# STM3205P_Connectors.net
KiCad netlist of a schematic drawn in Altium Designer
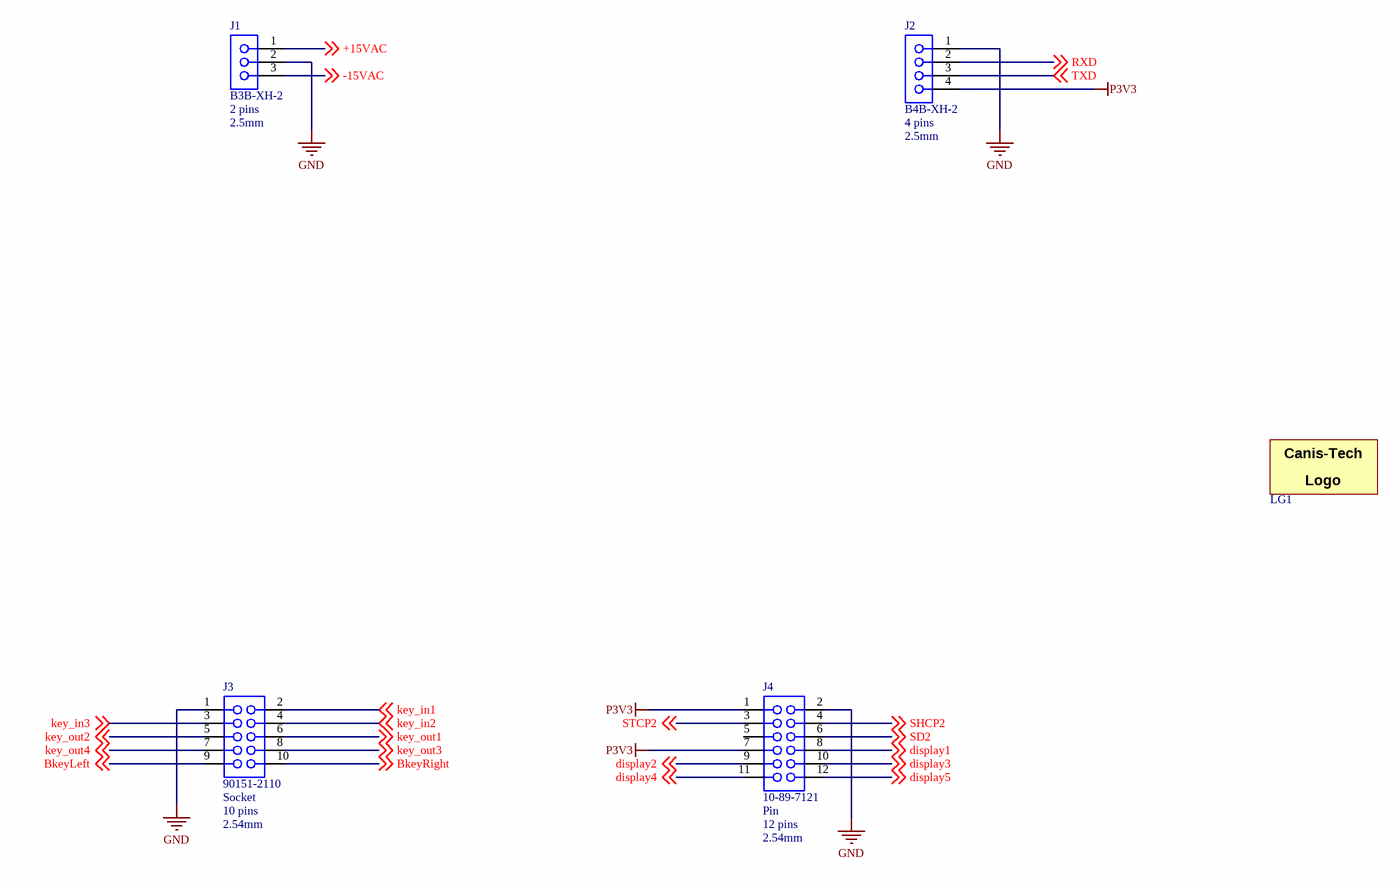
[diagram p0: STM3205P_Connectors.SchDoc]

(export (version "E")
  (design (tool "Eeschema 10.0.6"))
  (components
    (comp (ref "J1")
      (value "B3B-XH-2")
      (footprint "CONXH03STRMALE_2.5")
      (description "XH Connector 3 POS HDR VERT 2.5mm")
      (fields
        (field (name "PARTNUMBER1") "B3B-XH-2")
        (field (name "PINS") "2 pins")
        (field (name "PITCH") "2.5mm")
        (field (name "PUBLISHER") "Lucas Moraes")
      )
      (libsource (lib "XHConnector") (part "B3B-XH-2"))
    )
    (comp (ref "J2")
      (value "B4B-XH-2")
      (footprint "CONXH04STRMALE_2.5")
      (description "XH Connector 4 POS HDR VERT 2.5mm")
      (fields
        (field (name "PARTNUMBER1") "B4B-XH-2")
        (field (name "PINS") "4 pins")
        (field (name "PITCH") "2.5mm")
        (field (name "PUBLISHER") "Lucas Moraes")
      )
      (libsource (lib "XHConnector") (part "B4B-XH-2"))
    )
    (comp (ref "J3")
      (value "90151-2110")
      (footprint "CONDIL10STRFEMALE_100_100")
      (description "Headers & Wire Housings C-Grid PCB Conn Dual Row Vertical 10Ckt")
      (fields
        (field (name "PARTNUMBER1") "90151-2110")
        (field (name "TYPE") "Socket")
        (field (name "PINS") "10 pins")
        (field (name "PITCH") "2.54mm")
        (field (name "PUBLISHER") "Lucas Moraes")
      )
      (libsource (lib "HeaderSocket") (part "90151-2110"))
    )
    (comp (ref "J4")
      (value "10-89-7121")
      (footprint "CONDIL12STRMALE_100_100")
      (description "Headers & Wire Housings C-Grid PCB Conn SR V onn SR Vt Tn-A 12Ckt")
      (fields
        (field (name "PARTNUMBER1") "10-89-7121")
        (field (name "TYPE") "Pin")
        (field (name "PINS") "12 pins")
        (field (name "PITCH") "2.54mm")
        (field (name "PUBLISHER") "Lucas Moraes")
      )
      (libsource (lib "HeaderPin") (part "10-89-7121"))
    )
    (comp (ref "LG1")
      (value "Canis-Tech Logo")
      (footprint "CT Logo 400th")
      (description "Canis-Tech LOGO")
      (fields (field (name "PUBLISHER") "Lucas Moraes"))
      (libsource (lib "LocalSymbols") (part "Canis-Tech Logo"))
    )
  )
  (nets
    (net (code "1") (name "+15VAC") (class "Default")
      (node (ref "J1") (pin "1") (pinfunction "1_1") (pintype "passive"))
    )
    (net (code "2") (name "-15VAC") (class "Default")
      (node (ref "J1") (pin "3") (pinfunction "3_3") (pintype "passive"))
    )
    (net (code "3") (name "BkeyLeft") (class "Default")
      (node (ref "J3") (pin "9") (pinfunction "9_9") (pintype "passive"))
    )
    (net (code "4") (name "BkeyRight") (class "Default")
      (node (ref "J3") (pin "10") (pinfunction "10_10") (pintype "passive"))
    )
    (net (code "5") (name "GND") (class "Default")
      (node (ref "J1") (pin "2") (pinfunction "2_2") (pintype "passive"))
      (node (ref "J2") (pin "1") (pinfunction "1_1") (pintype "passive"))
      (node (ref "J3") (pin "1") (pinfunction "1_1") (pintype "passive"))
      (node (ref "J4") (pin "2") (pinfunction "2_2") (pintype "passive"))
    )
    (net (code "6") (name "P3V3") (class "Default")
      (node (ref "J2") (pin "4") (pinfunction "4_4") (pintype "passive"))
      (node (ref "J4") (pin "1") (pinfunction "1_1") (pintype "passive"))
      (node (ref "J4") (pin "7") (pinfunction "7_7") (pintype "passive"))
    )
    (net (code "7") (name "RXD") (class "Default")
      (node (ref "J2") (pin "2") (pinfunction "2_2") (pintype "passive"))
    )
    (net (code "8") (name "SD2") (class "Default")
      (node (ref "J4") (pin "6") (pinfunction "6_6") (pintype "passive"))
    )
    (net (code "9") (name "SHCP2") (class "Default")
      (node (ref "J4") (pin "4") (pinfunction "4_4") (pintype "passive"))
    )
    (net (code "10") (name "STCP2") (class "Default")
      (node (ref "J4") (pin "3") (pinfunction "3_3") (pintype "passive"))
    )
    (net (code "11") (name "TXD") (class "Default")
      (node (ref "J2") (pin "3") (pinfunction "3_3") (pintype "passive"))
    )
    (net (code "12") (name "display1") (class "Default")
      (node (ref "J4") (pin "8") (pinfunction "8_8") (pintype "passive"))
    )
    (net (code "13") (name "display2") (class "Default")
      (node (ref "J4") (pin "9") (pinfunction "9_9") (pintype "passive"))
    )
    (net (code "14") (name "display3") (class "Default")
      (node (ref "J4") (pin "10") (pinfunction "10_10") (pintype "passive"))
    )
    (net (code "15") (name "display4") (class "Default")
      (node (ref "J4") (pin "11") (pinfunction "11_11") (pintype "passive"))
    )
    (net (code "16") (name "display5") (class "Default")
      (node (ref "J4") (pin "12") (pinfunction "12_12") (pintype "passive"))
    )
    (net (code "17") (name "key_in1") (class "Default")
      (node (ref "J3") (pin "2") (pinfunction "2_2") (pintype "passive"))
    )
    (net (code "18") (name "key_in2") (class "Default")
      (node (ref "J3") (pin "4") (pinfunction "4_4") (pintype "passive"))
    )
    (net (code "19") (name "key_in3") (class "Default")
      (node (ref "J3") (pin "3") (pinfunction "3_3") (pintype "passive"))
    )
    (net (code "20") (name "key_out1") (class "Default")
      (node (ref "J3") (pin "6") (pinfunction "6_6") (pintype "passive"))
    )
    (net (code "21") (name "key_out2") (class "Default")
      (node (ref "J3") (pin "5") (pinfunction "5_5") (pintype "passive"))
    )
    (net (code "22") (name "key_out3") (class "Default")
      (node (ref "J3") (pin "8") (pinfunction "8_8") (pintype "passive"))
    )
    (net (code "23") (name "key_out4") (class "Default")
      (node (ref "J3") (pin "7") (pinfunction "7_7") (pintype "passive"))
    )
    (net (code "24") (name "unconnected-(J4-Pad5)") (class "Default")
      (node (ref "J4") (pin "5") (pinfunction "5_5") (pintype "passive"))
    )
  )
)
